# indication.net
KiCad netlist of a schematic drawn in EAGLE
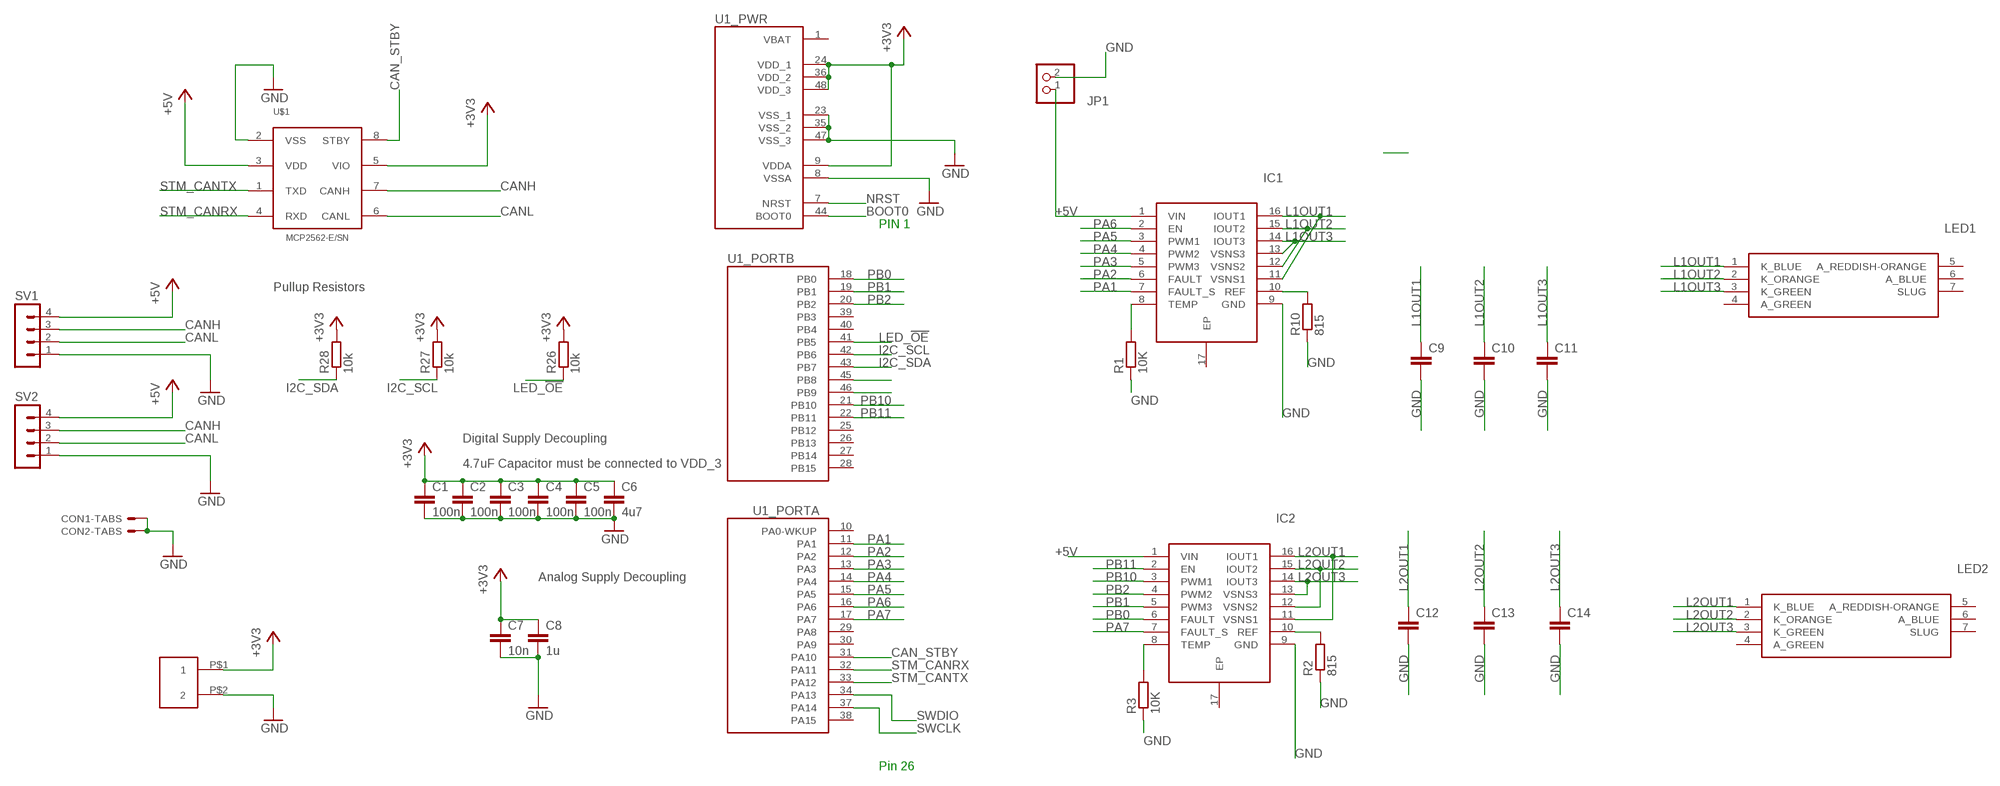
[diagram p0: schematic, sheet 1]

(export (version "E")
  (design (tool "Eeschema 10.0.6"))
  (components
    (comp (ref "C1")
      (value "100n")
      (footprint "eagle-import:C0805")
      (libsource (lib "eagle-import") (part "resistor_348_C-EUC0805"))
    )
    (comp (ref "C2")
      (value "100n")
      (footprint "eagle-import:C0805")
      (libsource (lib "eagle-import") (part "resistor_348_C-EUC0805"))
    )
    (comp (ref "C3")
      (value "100n")
      (footprint "eagle-import:C0805")
      (libsource (lib "eagle-import") (part "resistor_348_C-EUC0805"))
    )
    (comp (ref "C4")
      (value "100n")
      (footprint "eagle-import:C0805")
      (libsource (lib "eagle-import") (part "resistor_348_C-EUC0805"))
    )
    (comp (ref "C5")
      (value "100n")
      (footprint "eagle-import:C0805")
      (libsource (lib "eagle-import") (part "resistor_348_C-EUC0805"))
    )
    (comp (ref "C6")
      (value "4u7")
      (footprint "eagle-import:C0805")
      (libsource (lib "eagle-import") (part "resistor_348_C-EUC0805"))
    )
    (comp (ref "C7")
      (value "10n")
      (footprint "eagle-import:C0805")
      (libsource (lib "eagle-import") (part "resistor_348_C-EUC0805"))
    )
    (comp (ref "C8")
      (value "1u")
      (footprint "eagle-import:C0805")
      (libsource (lib "eagle-import") (part "resistor_348_C-EUC0805"))
    )
    (comp (ref "C9")
      (value "C-EUC0805")
      (footprint "eagle-import:C0805")
      (libsource (lib "eagle-import") (part "C-EUC0805"))
    )
    (comp (ref "C10")
      (value "C-EUC0805")
      (footprint "eagle-import:C0805")
      (libsource (lib "eagle-import") (part "C-EUC0805"))
    )
    (comp (ref "C11")
      (value "C-EUC0805")
      (footprint "eagle-import:C0805")
      (libsource (lib "eagle-import") (part "C-EUC0805"))
    )
    (comp (ref "C12")
      (value "C-EUC0805")
      (footprint "eagle-import:C0805")
      (libsource (lib "eagle-import") (part "C-EUC0805"))
    )
    (comp (ref "C13")
      (value "C-EUC0805")
      (footprint "eagle-import:C0805")
      (libsource (lib "eagle-import") (part "C-EUC0805"))
    )
    (comp (ref "C14")
      (value "C-EUC0805")
      (footprint "eagle-import:C0805")
      (libsource (lib "eagle-import") (part "C-EUC0805"))
    )
    (comp (ref "CON1")
      (value "SM04B-GHS-TB")
      (footprint "eagle-import:SM04B-GHS-TB")
      (libsource (lib "eagle-import") (part "SM04B-GHS-TB"))
    )
    (comp (ref "CON2")
      (value "SM04B-GHS-TB")
      (footprint "eagle-import:SM04B-GHS-TB")
      (libsource (lib "eagle-import") (part "SM04B-GHS-TB"))
    )
    (comp (ref "IC1")
      (value "TPS92630QPWPRQ1")
      (footprint "eagle-import:SOP65P640X120-17N")
      (fields (field (name "MOUSER_PART_NUMBER") "595-TPS92630QPWPRQ1"))
      (libsource (lib "eagle-import") (part "TPS92630QPWPRQ1"))
    )
    (comp (ref "IC2")
      (value "TPS92630QPWPRQ1")
      (footprint "eagle-import:SOP65P640X120-17N")
      (fields (field (name "MOUSER_PART_NUMBER") "595-TPS92630QPWPRQ1"))
      (libsource (lib "eagle-import") (part "TPS92630QPWPRQ1"))
    )
    (comp (ref "JP1")
      (value "PINHD-1X2")
      (footprint "eagle-import:1X02")
      (libsource (lib "eagle-import") (part "PINHD-1X2"))
    )
    (comp (ref "LED1")
      (value "AAAF5051-05")
      (footprint "eagle-import:AAAF505105")
      (fields (field (name "MOUSER_PART_NUMBER") "604-AAAF5051-05"))
      (libsource (lib "eagle-import") (part "AAAF5051-05"))
    )
    (comp (ref "LED2")
      (value "AAAF5051-05")
      (footprint "eagle-import:AAAF505105")
      (fields (field (name "MOUSER_PART_NUMBER") "604-AAAF5051-05"))
      (libsource (lib "eagle-import") (part "AAAF5051-05"))
    )
    (comp (ref "R1")
      (value "10K")
      (footprint "eagle-import:R0805")
      (libsource (lib "eagle-import") (part "R-EU_R0805"))
    )
    (comp (ref "R2")
      (value "815")
      (footprint "eagle-import:R0805")
      (libsource (lib "eagle-import") (part "R-EU_R0805"))
    )
    (comp (ref "R3")
      (value "10K")
      (footprint "eagle-import:R0805")
      (libsource (lib "eagle-import") (part "R-EU_R0805"))
    )
    (comp (ref "R10")
      (value "815")
      (footprint "eagle-import:R0805")
      (libsource (lib "eagle-import") (part "R-EU_R0805"))
    )
    (comp (ref "R26")
      (value "10k")
      (footprint "eagle-import:R0805")
      (libsource (lib "eagle-import") (part "R-EU_R0805"))
    )
    (comp (ref "R27")
      (value "10k")
      (footprint "eagle-import:R0805")
      (libsource (lib "eagle-import") (part "R-EU_R0805"))
    )
    (comp (ref "R28")
      (value "10k")
      (footprint "eagle-import:R0805")
      (libsource (lib "eagle-import") (part "R-EU_R0805"))
    )
    (comp (ref "SV1")
      (value "MA04-1")
      (footprint "eagle-import:MA04-1")
      (libsource (lib "eagle-import") (part "MA04-1"))
    )
    (comp (ref "SV2")
      (value "MA04-1")
      (footprint "eagle-import:MA04-1")
      (libsource (lib "eagle-import") (part "MA04-1"))
    )
    (comp (ref "U$1")
      (value "MCP2562-E/SN")
      (footprint "eagle-import:SOIC8")
      (libsource (lib "eagle-import") (part "MCP2562-E/SN"))
    )
    (comp (ref "U$4")
      (value "TE-CONN_5-103669-1")
      (footprint "eagle-import:TE-CONN_5-103669-1")
      (libsource (lib "eagle-import") (part "TE-CONN_5-103669-1"))
    )
    (comp (ref "U1")
      (value "STM32F103CB")
      (footprint "eagle-import:LQFP48")
      (libsource (lib "eagle-import") (part "STM32F103CB"))
    )
  )
  (nets
    (net (code "1") (name "+3V3") (class "Default")
      (node (ref "C1") (pin "1") (pinfunction "1_1") (pintype "passive"))
      (node (ref "C2") (pin "1") (pinfunction "1_1") (pintype "passive"))
      (node (ref "C3") (pin "1") (pinfunction "1_1") (pintype "passive"))
      (node (ref "C4") (pin "1") (pinfunction "1_1") (pintype "passive"))
      (node (ref "C5") (pin "1") (pinfunction "1_1") (pintype "passive"))
      (node (ref "C6") (pin "1") (pinfunction "1_1") (pintype "passive"))
      (node (ref "C7") (pin "1") (pinfunction "1_1") (pintype "passive"))
      (node (ref "C8") (pin "1") (pinfunction "1_1") (pintype "passive"))
      (node (ref "R26") (pin "2") (pinfunction "2_2") (pintype "passive"))
      (node (ref "R27") (pin "2") (pinfunction "2_2") (pintype "passive"))
      (node (ref "R28") (pin "2") (pinfunction "2_2") (pintype "passive"))
      (node (ref "U$1") (pin "5") (pinfunction "VIO_5") (pintype "bidirectional"))
      (node (ref "U$4") (pin "P$1") (pinfunction "1_P$1") (pintype "bidirectional"))
      (node (ref "U1") (pin "24") (pinfunction "VDD_1_24") (pintype "bidirectional"))
      (node (ref "U1") (pin "36") (pinfunction "VDD_2_36") (pintype "bidirectional"))
      (node (ref "U1") (pin "48") (pinfunction "VDD_3_48") (pintype "bidirectional"))
      (node (ref "U1") (pin "9") (pinfunction "VDDA_9") (pintype "bidirectional"))
    )
    (net (code "2") (name "+5V") (class "Default")
      (node (ref "IC1") (pin "1") (pinfunction "VIN_1") (pintype "bidirectional"))
      (node (ref "IC2") (pin "1") (pinfunction "VIN_1") (pintype "bidirectional"))
      (node (ref "JP1") (pin "1") (pinfunction "1_1") (pintype "passive"))
      (node (ref "SV1") (pin "4") (pinfunction "4_4") (pintype "passive"))
      (node (ref "SV2") (pin "4") (pinfunction "4_4") (pintype "passive"))
      (node (ref "U$1") (pin "3") (pinfunction "VDD_3") (pintype "bidirectional"))
    )
    (net (code "3") (name "/BOOT0") (class "Default")
      (node (ref "U1") (pin "44") (pinfunction "BOOT0_44") (pintype "bidirectional"))
    )
    (net (code "4") (name "/CANH") (class "Default")
      (node (ref "SV1") (pin "3") (pinfunction "3_3") (pintype "passive"))
      (node (ref "SV2") (pin "3") (pinfunction "3_3") (pintype "passive"))
      (node (ref "U$1") (pin "7") (pinfunction "CANH_7") (pintype "bidirectional"))
    )
    (net (code "5") (name "/CANL") (class "Default")
      (node (ref "SV1") (pin "2") (pinfunction "2_2") (pintype "passive"))
      (node (ref "SV2") (pin "2") (pinfunction "2_2") (pintype "passive"))
      (node (ref "U$1") (pin "6") (pinfunction "CANL_6") (pintype "bidirectional"))
    )
    (net (code "6") (name "/CAN_STBY") (class "Default")
      (node (ref "U$1") (pin "8") (pinfunction "STBY_8") (pintype "bidirectional"))
      (node (ref "U1") (pin "31") (pinfunction "PA10_31") (pintype "bidirectional"))
    )
    (net (code "7") (name "/I2C_SCL") (class "Default")
      (node (ref "R27") (pin "1") (pinfunction "1_1") (pintype "passive"))
      (node (ref "U1") (pin "42") (pinfunction "PB6_42") (pintype "bidirectional"))
    )
    (net (code "8") (name "/I2C_SDA") (class "Default")
      (node (ref "R28") (pin "1") (pinfunction "1_1") (pintype "passive"))
      (node (ref "U1") (pin "43") (pinfunction "PB7_43") (pintype "bidirectional"))
    )
    (net (code "9") (name "/L1OUT1") (class "Default")
      (node (ref "C9") (pin "1") (pinfunction "1_1") (pintype "passive"))
      (node (ref "IC1") (pin "11") (pinfunction "VSNS1_11") (pintype "bidirectional"))
      (node (ref "IC1") (pin "16") (pinfunction "IOUT1_16") (pintype "bidirectional"))
      (node (ref "LED1") (pin "1") (pinfunction "K_BLUE_1") (pintype "bidirectional"))
    )
    (net (code "10") (name "/L1OUT2") (class "Default")
      (node (ref "C10") (pin "1") (pinfunction "1_1") (pintype "passive"))
      (node (ref "IC1") (pin "12") (pinfunction "VSNS2_12") (pintype "bidirectional"))
      (node (ref "IC1") (pin "15") (pinfunction "IOUT2_15") (pintype "bidirectional"))
      (node (ref "LED1") (pin "2") (pinfunction "K_ORANGE_2") (pintype "bidirectional"))
    )
    (net (code "11") (name "/L1OUT3") (class "Default")
      (node (ref "C11") (pin "1") (pinfunction "1_1") (pintype "passive"))
      (node (ref "IC1") (pin "13") (pinfunction "VSNS3_13") (pintype "bidirectional"))
      (node (ref "IC1") (pin "14") (pinfunction "IOUT3_14") (pintype "bidirectional"))
      (node (ref "LED1") (pin "3") (pinfunction "K_GREEN_3") (pintype "bidirectional"))
    )
    (net (code "12") (name "/L2OUT1") (class "Default")
      (node (ref "C12") (pin "1") (pinfunction "1_1") (pintype "passive"))
      (node (ref "IC2") (pin "11") (pinfunction "VSNS1_11") (pintype "bidirectional"))
      (node (ref "IC2") (pin "16") (pinfunction "IOUT1_16") (pintype "bidirectional"))
      (node (ref "LED2") (pin "1") (pinfunction "K_BLUE_1") (pintype "bidirectional"))
    )
    (net (code "13") (name "/L2OUT2") (class "Default")
      (node (ref "C13") (pin "1") (pinfunction "1_1") (pintype "passive"))
      (node (ref "IC2") (pin "12") (pinfunction "VSNS2_12") (pintype "bidirectional"))
      (node (ref "IC2") (pin "15") (pinfunction "IOUT2_15") (pintype "bidirectional"))
      (node (ref "LED2") (pin "2") (pinfunction "K_ORANGE_2") (pintype "bidirectional"))
    )
    (net (code "14") (name "/L2OUT3") (class "Default")
      (node (ref "C14") (pin "1") (pinfunction "1_1") (pintype "passive"))
      (node (ref "IC2") (pin "13") (pinfunction "VSNS3_13") (pintype "bidirectional"))
      (node (ref "IC2") (pin "14") (pinfunction "IOUT3_14") (pintype "bidirectional"))
      (node (ref "LED2") (pin "3") (pinfunction "K_GREEN_3") (pintype "bidirectional"))
    )
    (net (code "15") (name "/LED_~{OE}") (class "Default")
      (node (ref "R26") (pin "1") (pinfunction "1_1") (pintype "passive"))
      (node (ref "U1") (pin "41") (pinfunction "PB5_41") (pintype "bidirectional"))
    )
    (net (code "16") (name "/NRST") (class "Default")
      (node (ref "U1") (pin "7") (pinfunction "NRST_7") (pintype "bidirectional"))
    )
    (net (code "17") (name "/PA1") (class "Default")
      (node (ref "IC1") (pin "7") (pinfunction "FAULT_S_7") (pintype "bidirectional"))
      (node (ref "U1") (pin "11") (pinfunction "PA1_11") (pintype "bidirectional"))
    )
    (net (code "18") (name "/PA2") (class "Default")
      (node (ref "IC1") (pin "6") (pinfunction "FAULT_6") (pintype "bidirectional"))
      (node (ref "U1") (pin "12") (pinfunction "PA2_12") (pintype "bidirectional"))
    )
    (net (code "19") (name "/PA3") (class "Default")
      (node (ref "IC1") (pin "5") (pinfunction "PWM3_5") (pintype "bidirectional"))
      (node (ref "U1") (pin "13") (pinfunction "PA3_13") (pintype "bidirectional"))
    )
    (net (code "20") (name "/PA4") (class "Default")
      (node (ref "IC1") (pin "4") (pinfunction "PWM2_4") (pintype "bidirectional"))
      (node (ref "U1") (pin "14") (pinfunction "PA4_14") (pintype "bidirectional"))
    )
    (net (code "21") (name "/PA5") (class "Default")
      (node (ref "IC1") (pin "3") (pinfunction "PWM1_3") (pintype "bidirectional"))
      (node (ref "U1") (pin "15") (pinfunction "PA5_15") (pintype "bidirectional"))
    )
    (net (code "22") (name "/PA6") (class "Default")
      (node (ref "IC1") (pin "2") (pinfunction "EN_2") (pintype "bidirectional"))
      (node (ref "U1") (pin "16") (pinfunction "PA6_16") (pintype "bidirectional"))
    )
    (net (code "23") (name "/PA7") (class "Default")
      (node (ref "IC2") (pin "7") (pinfunction "FAULT_S_7") (pintype "bidirectional"))
      (node (ref "U1") (pin "17") (pinfunction "PA7_17") (pintype "bidirectional"))
    )
    (net (code "24") (name "/PB0") (class "Default")
      (node (ref "IC2") (pin "6") (pinfunction "FAULT_6") (pintype "bidirectional"))
      (node (ref "U1") (pin "18") (pinfunction "PB0_18") (pintype "bidirectional"))
    )
    (net (code "25") (name "/PB1") (class "Default")
      (node (ref "IC2") (pin "5") (pinfunction "PWM3_5") (pintype "bidirectional"))
      (node (ref "U1") (pin "19") (pinfunction "PB1_19") (pintype "bidirectional"))
    )
    (net (code "26") (name "/PB2") (class "Default")
      (node (ref "IC2") (pin "4") (pinfunction "PWM2_4") (pintype "bidirectional"))
      (node (ref "U1") (pin "20") (pinfunction "PB2_20") (pintype "bidirectional"))
    )
    (net (code "27") (name "/PB10") (class "Default")
      (node (ref "IC2") (pin "3") (pinfunction "PWM1_3") (pintype "bidirectional"))
      (node (ref "U1") (pin "21") (pinfunction "PB10_21") (pintype "bidirectional"))
    )
    (net (code "28") (name "/PB11") (class "Default")
      (node (ref "IC2") (pin "2") (pinfunction "EN_2") (pintype "bidirectional"))
      (node (ref "U1") (pin "22") (pinfunction "PB11_22") (pintype "bidirectional"))
    )
    (net (code "29") (name "/STM_CANRX") (class "Default")
      (node (ref "U$1") (pin "4") (pinfunction "RXD_4") (pintype "bidirectional"))
      (node (ref "U1") (pin "32") (pinfunction "PA11_32") (pintype "bidirectional"))
    )
    (net (code "30") (name "/STM_CANTX") (class "Default")
      (node (ref "U$1") (pin "1") (pinfunction "TXD_1") (pintype "bidirectional"))
      (node (ref "U1") (pin "33") (pinfunction "PA12_33") (pintype "bidirectional"))
    )
    (net (code "31") (name "/SWCLK") (class "Default")
      (node (ref "U1") (pin "37") (pinfunction "PA14_37") (pintype "bidirectional"))
    )
    (net (code "32") (name "/SWDIO") (class "Default")
      (node (ref "U1") (pin "34") (pinfunction "PA13_34") (pintype "bidirectional"))
    )
    (net (code "33") (name "GND") (class "Default")
      (node (ref "C1") (pin "2") (pinfunction "2_2") (pintype "passive"))
      (node (ref "C10") (pin "2") (pinfunction "2_2") (pintype "passive"))
      (node (ref "C11") (pin "2") (pinfunction "2_2") (pintype "passive"))
      (node (ref "C12") (pin "2") (pinfunction "2_2") (pintype "passive"))
      (node (ref "C13") (pin "2") (pinfunction "2_2") (pintype "passive"))
      (node (ref "C14") (pin "2") (pinfunction "2_2") (pintype "passive"))
      (node (ref "C2") (pin "2") (pinfunction "2_2") (pintype "passive"))
      (node (ref "C3") (pin "2") (pinfunction "2_2") (pintype "passive"))
      (node (ref "C4") (pin "2") (pinfunction "2_2") (pintype "passive"))
      (node (ref "C5") (pin "2") (pinfunction "2_2") (pintype "passive"))
      (node (ref "C6") (pin "2") (pinfunction "2_2") (pintype "passive"))
      (node (ref "C7") (pin "2") (pinfunction "2_2") (pintype "passive"))
      (node (ref "C8") (pin "2") (pinfunction "2_2") (pintype "passive"))
      (node (ref "C9") (pin "2") (pinfunction "2_2") (pintype "passive"))
      (node (ref "CON1") (pin "P$5") (pinfunction "S_P$5") (pintype "passive"))
      (node (ref "CON1") (pin "P$6") (pinfunction "S_P$6") (pintype "passive"))
      (node (ref "CON2") (pin "P$5") (pinfunction "S_P$5") (pintype "passive"))
      (node (ref "CON2") (pin "P$6") (pinfunction "S_P$6") (pintype "passive"))
      (node (ref "IC1") (pin "9") (pinfunction "GND_9") (pintype "bidirectional"))
      (node (ref "IC2") (pin "9") (pinfunction "GND_9") (pintype "bidirectional"))
      (node (ref "JP1") (pin "2") (pinfunction "2_2") (pintype "passive"))
      (node (ref "R1") (pin "1") (pinfunction "1_1") (pintype "passive"))
      (node (ref "R10") (pin "1") (pinfunction "1_1") (pintype "passive"))
      (node (ref "R2") (pin "1") (pinfunction "1_1") (pintype "passive"))
      (node (ref "R3") (pin "1") (pinfunction "1_1") (pintype "passive"))
      (node (ref "SV1") (pin "1") (pinfunction "1_1") (pintype "passive"))
      (node (ref "SV2") (pin "1") (pinfunction "1_1") (pintype "passive"))
      (node (ref "U$1") (pin "2") (pinfunction "VSS_2") (pintype "bidirectional"))
      (node (ref "U$4") (pin "P$2") (pinfunction "2_P$2") (pintype "bidirectional"))
      (node (ref "U1") (pin "23") (pinfunction "VSS_1_23") (pintype "bidirectional"))
      (node (ref "U1") (pin "35") (pinfunction "VSS_2_35") (pintype "bidirectional"))
      (node (ref "U1") (pin "47") (pinfunction "VSS_3_47") (pintype "bidirectional"))
      (node (ref "U1") (pin "8") (pinfunction "VSSA_8") (pintype "bidirectional"))
    )
    (net (code "34") (name "Net-(IC1-REF)") (class "Default")
      (node (ref "IC1") (pin "10") (pinfunction "REF_10") (pintype "bidirectional"))
      (node (ref "R10") (pin "2") (pinfunction "2_2") (pintype "passive"))
    )
    (net (code "35") (name "Net-(IC1-TEMP)") (class "Default")
      (node (ref "IC1") (pin "8") (pinfunction "TEMP_8") (pintype "bidirectional"))
      (node (ref "R1") (pin "2") (pinfunction "2_2") (pintype "passive"))
    )
    (net (code "36") (name "Net-(IC2-REF)") (class "Default")
      (node (ref "IC2") (pin "10") (pinfunction "REF_10") (pintype "bidirectional"))
      (node (ref "R2") (pin "2") (pinfunction "2_2") (pintype "passive"))
    )
    (net (code "37") (name "Net-(IC2-TEMP)") (class "Default")
      (node (ref "IC2") (pin "8") (pinfunction "TEMP_8") (pintype "bidirectional"))
      (node (ref "R3") (pin "2") (pinfunction "2_2") (pintype "passive"))
    )
    (net (code "38") (name "unconnected-(IC1-EP-Pad17)") (class "Default")
      (node (ref "IC1") (pin "17") (pinfunction "EP_17") (pintype "bidirectional"))
    )
    (net (code "39") (name "unconnected-(IC2-EP-Pad17)") (class "Default")
      (node (ref "IC2") (pin "17") (pinfunction "EP_17") (pintype "bidirectional"))
    )
    (net (code "40") (name "unconnected-(LED1-A_BLUE-Pad6)") (class "Default")
      (node (ref "LED1") (pin "6") (pinfunction "A_BLUE_6") (pintype "bidirectional"))
    )
    (net (code "41") (name "unconnected-(LED1-A_GREEN-Pad4)") (class "Default")
      (node (ref "LED1") (pin "4") (pinfunction "A_GREEN_4") (pintype "bidirectional"))
    )
    (net (code "42") (name "unconnected-(LED1-A_REDDISH-ORANGE-Pad5)") (class "Default")
      (node (ref "LED1") (pin "5") (pinfunction "A_REDDISH-ORANGE_5") (pintype "bidirectional"))
    )
    (net (code "43") (name "unconnected-(LED1-SLUG-Pad7)") (class "Default")
      (node (ref "LED1") (pin "7") (pinfunction "SLUG_7") (pintype "bidirectional"))
    )
    (net (code "44") (name "unconnected-(LED2-A_BLUE-Pad6)") (class "Default")
      (node (ref "LED2") (pin "6") (pinfunction "A_BLUE_6") (pintype "bidirectional"))
    )
    (net (code "45") (name "unconnected-(LED2-A_GREEN-Pad4)") (class "Default")
      (node (ref "LED2") (pin "4") (pinfunction "A_GREEN_4") (pintype "bidirectional"))
    )
    (net (code "46") (name "unconnected-(LED2-A_REDDISH-ORANGE-Pad5)") (class "Default")
      (node (ref "LED2") (pin "5") (pinfunction "A_REDDISH-ORANGE_5") (pintype "bidirectional"))
    )
    (net (code "47") (name "unconnected-(LED2-SLUG-Pad7)") (class "Default")
      (node (ref "LED2") (pin "7") (pinfunction "SLUG_7") (pintype "bidirectional"))
    )
    (net (code "48") (name "unconnected-(U1A-PA0-WKUP-Pad10)") (class "Default")
      (node (ref "U1") (pin "10") (pinfunction "PA0-WKUP_10") (pintype "bidirectional"))
    )
    (net (code "49") (name "unconnected-(U1A-PA8-Pad29)") (class "Default")
      (node (ref "U1") (pin "29") (pinfunction "PA8_29") (pintype "bidirectional"))
    )
    (net (code "50") (name "unconnected-(U1A-PA9-Pad30)") (class "Default")
      (node (ref "U1") (pin "30") (pinfunction "PA9_30") (pintype "bidirectional"))
    )
    (net (code "51") (name "unconnected-(U1A-PA15-Pad38)") (class "Default")
      (node (ref "U1") (pin "38") (pinfunction "PA15_38") (pintype "bidirectional"))
    )
    (net (code "52") (name "unconnected-(U1B-PB3-Pad39)") (class "Default")
      (node (ref "U1") (pin "39") (pinfunction "PB3_39") (pintype "bidirectional"))
    )
    (net (code "53") (name "unconnected-(U1B-PB4-Pad40)") (class "Default")
      (node (ref "U1") (pin "40") (pinfunction "PB4_40") (pintype "bidirectional"))
    )
    (net (code "54") (name "unconnected-(U1B-PB8-Pad45)") (class "Default")
      (node (ref "U1") (pin "45") (pinfunction "PB8_45") (pintype "bidirectional"))
    )
    (net (code "55") (name "unconnected-(U1B-PB9-Pad46)") (class "Default")
      (node (ref "U1") (pin "46") (pinfunction "PB9_46") (pintype "bidirectional"))
    )
    (net (code "56") (name "unconnected-(U1B-PB12-Pad25)") (class "Default")
      (node (ref "U1") (pin "25") (pinfunction "PB12_25") (pintype "bidirectional"))
    )
    (net (code "57") (name "unconnected-(U1B-PB13-Pad26)") (class "Default")
      (node (ref "U1") (pin "26") (pinfunction "PB13_26") (pintype "bidirectional"))
    )
    (net (code "58") (name "unconnected-(U1B-PB14-Pad27)") (class "Default")
      (node (ref "U1") (pin "27") (pinfunction "PB14_27") (pintype "bidirectional"))
    )
    (net (code "59") (name "unconnected-(U1B-PB15-Pad28)") (class "Default")
      (node (ref "U1") (pin "28") (pinfunction "PB15_28") (pintype "bidirectional"))
    )
    (net (code "60") (name "unconnected-(U1D-VBAT-Pad1)") (class "Default")
      (node (ref "U1") (pin "1") (pinfunction "VBAT_1") (pintype "bidirectional"))
    )
  )
)
